# Voltage_Regulator.net
KiCad netlist of a schematic drawn in EAGLE
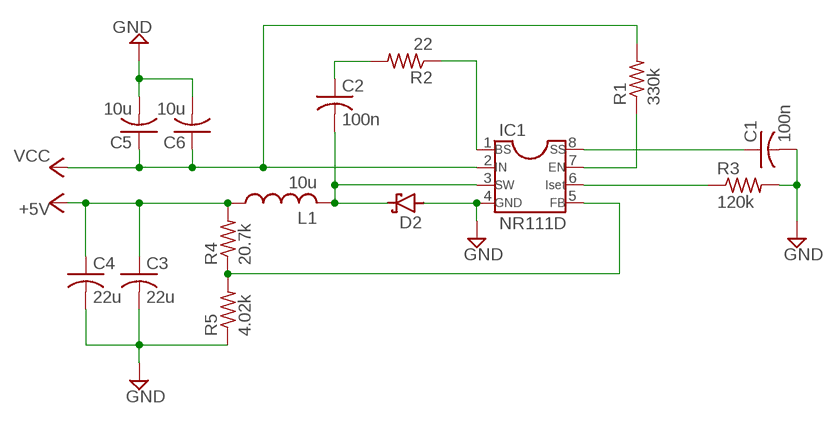
[diagram p0: schematic, sheet 1]

(export (version "E")
  (design (tool "Eeschema 10.0.6"))
  (components
    (comp (ref "C1")
      (value "100n")
      (footprint "eagle-import:C050-024X044")
      (libsource (lib "eagle-import") (part "C-US050-024X044"))
    )
    (comp (ref "C2")
      (value "100n")
      (footprint "eagle-import:C050-024X044")
      (libsource (lib "eagle-import") (part "C-US050-024X044"))
    )
    (comp (ref "C3")
      (value "22u")
      (footprint "eagle-import:C025-024X044")
      (libsource (lib "eagle-import") (part "C-US025-024X044"))
    )
    (comp (ref "C4")
      (value "22u")
      (footprint "eagle-import:C025-024X044")
      (libsource (lib "eagle-import") (part "C-US025-024X044"))
    )
    (comp (ref "C5")
      (value "10u")
      (footprint "eagle-import:C025-024X044")
      (libsource (lib "eagle-import") (part "C-US025-024X044"))
    )
    (comp (ref "C6")
      (value "10u")
      (footprint "eagle-import:C025-024X044")
      (libsource (lib "eagle-import") (part "C-US025-024X044"))
    )
    (comp (ref "D2")
      (value "SCHOTTKY-DIODEC4111-15")
      (footprint "eagle-import:C4111-15")
      (libsource (lib "eagle-import") (part "SCHOTTKY-DIODEC4111-15"))
    )
    (comp (ref "IC1")
      (value "NR111D")
      (footprint "eagle-import:DIL08")
      (libsource (lib "eagle-import") (part "DIL8"))
    )
    (comp (ref "L1")
      (value "10u")
      (footprint "eagle-import:INDRD650W105D880H1100B")
      (libsource (lib "eagle-import") (part "WURTHINDUCTOR1"))
    )
    (comp (ref "R1")
      (value "330k")
      (footprint "eagle-import:0204_7")
      (libsource (lib "eagle-import") (part "R-US_0204/7"))
    )
    (comp (ref "R2")
      (value "22")
      (footprint "eagle-import:0204_7")
      (libsource (lib "eagle-import") (part "R-US_0204/7"))
    )
    (comp (ref "R3")
      (value "120k")
      (footprint "eagle-import:0204_7")
      (libsource (lib "eagle-import") (part "R-US_0204/7"))
    )
    (comp (ref "R4")
      (value "20.7k")
      (footprint "eagle-import:0204_7")
      (libsource (lib "eagle-import") (part "R-US_0204/7"))
    )
    (comp (ref "R5")
      (value "4.02k")
      (footprint "eagle-import:0204_7")
      (libsource (lib "eagle-import") (part "R-US_0204/7"))
    )
  )
  (nets
    (net (code "1") (name "+5V") (class "Default")
      (node (ref "C3") (pin "1") (pinfunction "1_1") (pintype "passive"))
      (node (ref "C4") (pin "1") (pinfunction "1_1") (pintype "passive"))
      (node (ref "L1") (pin "1") (pinfunction "1_1") (pintype "passive"))
      (node (ref "R4") (pin "2") (pinfunction "2_2") (pintype "passive"))
    )
    (net (code "2") (name "GND") (class "Default")
      (node (ref "C1") (pin "2") (pinfunction "2_2") (pintype "passive"))
      (node (ref "C3") (pin "2") (pinfunction "2_2") (pintype "passive"))
      (node (ref "C4") (pin "2") (pinfunction "2_2") (pintype "passive"))
      (node (ref "C5") (pin "2") (pinfunction "2_2") (pintype "passive"))
      (node (ref "C6") (pin "2") (pinfunction "2_2") (pintype "passive"))
      (node (ref "D2") (pin "A") (pinfunction "A_A") (pintype "passive"))
      (node (ref "IC1") (pin "4") (pinfunction "GND_4") (pintype "passive"))
      (node (ref "R3") (pin "2") (pinfunction "2_2") (pintype "passive"))
      (node (ref "R5") (pin "1") (pinfunction "1_1") (pintype "passive"))
    )
    (net (code "3") (name "Net-(C2-Pad1)") (class "Default")
      (node (ref "C2") (pin "1") (pinfunction "1_1") (pintype "passive"))
      (node (ref "R2") (pin "2") (pinfunction "2_2") (pintype "passive"))
    )
    (net (code "4") (name "Net-(IC1-BS)") (class "Default")
      (node (ref "IC1") (pin "1") (pinfunction "BS_1") (pintype "passive"))
      (node (ref "R2") (pin "1") (pinfunction "1_1") (pintype "passive"))
    )
    (net (code "5") (name "Net-(IC1-EN)") (class "Default")
      (node (ref "IC1") (pin "7") (pinfunction "EN_7") (pintype "passive"))
      (node (ref "R1") (pin "1") (pinfunction "1_1") (pintype "passive"))
    )
    (net (code "6") (name "Net-(IC1-FB)") (class "Default")
      (node (ref "IC1") (pin "5") (pinfunction "FB_5") (pintype "passive"))
      (node (ref "R4") (pin "1") (pinfunction "1_1") (pintype "passive"))
      (node (ref "R5") (pin "2") (pinfunction "2_2") (pintype "passive"))
    )
    (net (code "7") (name "Net-(IC1-ISET)") (class "Default")
      (node (ref "IC1") (pin "6") (pinfunction "ISET_6") (pintype "passive"))
      (node (ref "R3") (pin "1") (pinfunction "1_1") (pintype "passive"))
    )
    (net (code "8") (name "Net-(IC1-SS)") (class "Default")
      (node (ref "C1") (pin "1") (pinfunction "1_1") (pintype "passive"))
      (node (ref "IC1") (pin "8") (pinfunction "SS_8") (pintype "passive"))
    )
    (net (code "9") (name "Net-(IC1-SW)") (class "Default")
      (node (ref "C2") (pin "2") (pinfunction "2_2") (pintype "passive"))
      (node (ref "D2") (pin "C") (pinfunction "C_C") (pintype "passive"))
      (node (ref "IC1") (pin "3") (pinfunction "SW_3") (pintype "passive"))
      (node (ref "L1") (pin "2") (pinfunction "2_2") (pintype "passive"))
    )
    (net (code "10") (name "VCC") (class "Default")
      (node (ref "C5") (pin "1") (pinfunction "1_1") (pintype "passive"))
      (node (ref "C6") (pin "1") (pinfunction "1_1") (pintype "passive"))
      (node (ref "IC1") (pin "2") (pinfunction "IN_2") (pintype "passive"))
      (node (ref "R1") (pin "2") (pinfunction "2_2") (pintype "passive"))
    )
  )
)
